# drandyhaas_logo.net
KiCad netlist of a schematic drawn in EAGLE
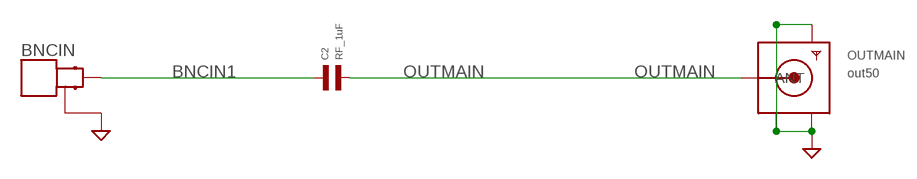
[diagram p0: schematic, sheet 1]

(export (version "E")
  (design (tool "Eeschema 10.0.6"))
  (components
    (comp (ref "BNCIN")
      (value "MOLEX_BNC_73100-0105")
      (footprint "eagle-import:MOLEX-BNC-73100-0105")
      (fields (field (name "MPN") "73100-0105"))
      (libsource (lib "eagle-import") (part "MOLEX_BNC_73100-0105"))
    )
    (comp (ref "C2")
      (value "RF_1uF")
      (footprint "eagle-import:C0402")
      (libsource (lib "eagle-import") (part "CAPACITOR_NP_0402"))
    )
    (comp (ref "OUTMAIN")
      (value "out50")
      (footprint "eagle-import:SMA_EDGELAUNCH")
      (libsource (lib "eagle-import") (part "SMACONNECTOR_EDGE"))
    )
  )
  (nets
    (net (code "1") (name "/BNCIN1") (class "Default")
      (node (ref "BNCIN") (pin "SIGNAL") (pinfunction "SIGNAL_SIGNAL") (pintype "bidirectional"))
      (node (ref "C2") (pin "P$1") (pinfunction "P$1_P$1") (pintype "passive"))
    )
    (net (code "2") (name "/OUTMAIN") (class "Default")
      (node (ref "C2") (pin "P$2") (pinfunction "P$2_P$2") (pintype "passive"))
      (node (ref "OUTMAIN") (pin "P") (pinfunction "ANT_P") (pintype "bidirectional"))
    )
    (net (code "3") (name "GND") (class "Default")
      (node (ref "BNCIN") (pin "GND1") (pinfunction "GND_GND1") (pintype "bidirectional"))
      (node (ref "BNCIN") (pin "GND2") (pinfunction "GND_GND2") (pintype "bidirectional"))
      (node (ref "OUTMAIN") (pin "GND@1") (pinfunction "GND4_GND@1") (pintype "power_in"))
      (node (ref "OUTMAIN") (pin "GND@2") (pinfunction "GND3_GND@2") (pintype "power_in"))
      (node (ref "OUTMAIN") (pin "GND@3") (pinfunction "GND2_GND@3") (pintype "power_in"))
      (node (ref "OUTMAIN") (pin "GND@4") (pinfunction "GND1_GND@4") (pintype "power_in"))
    )
  )
)
